# tiny13_charlie4_50mm_AAA_optical_diag_SM.net
KiCad netlist of a schematic drawn in EAGLE
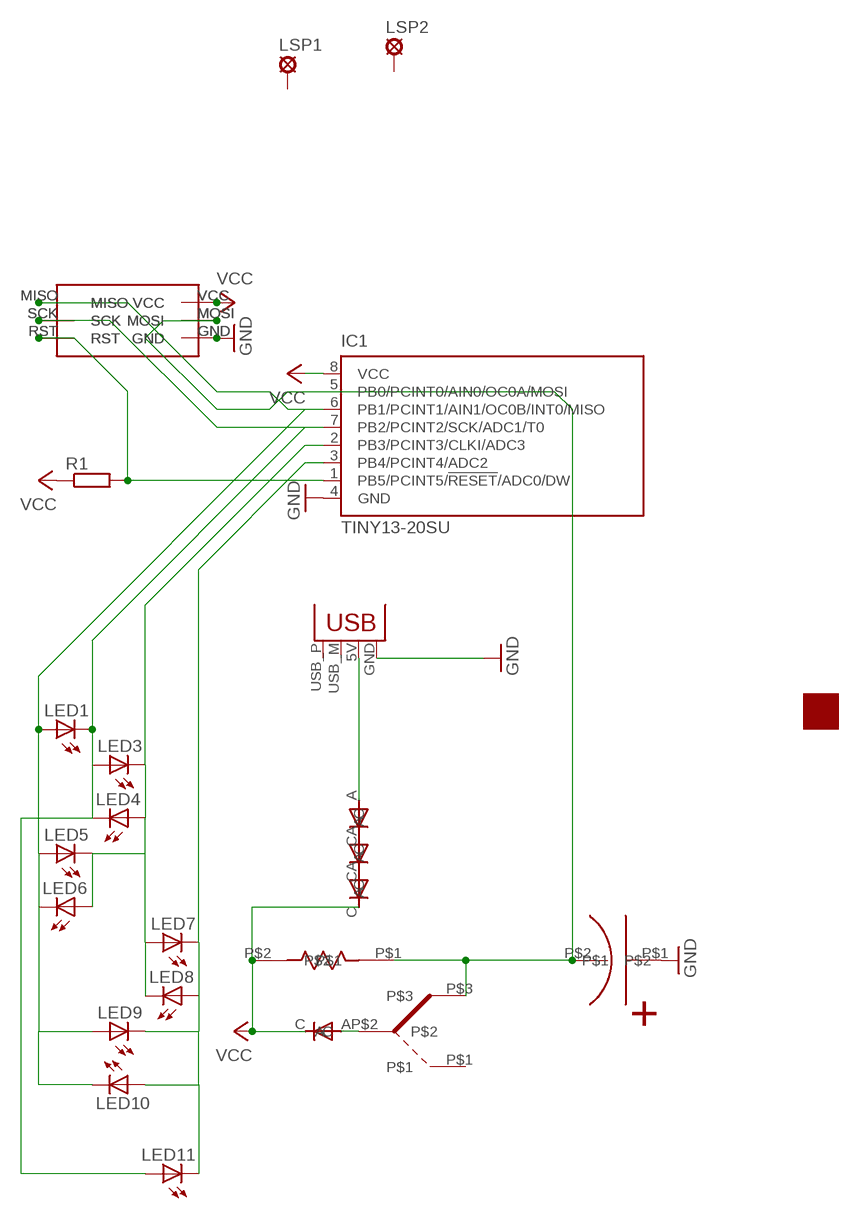
[diagram p0: schematic, sheet 1]

(export (version "E")
  (design (tool "Eeschema 10.0.6"))
  (components
    (comp (ref "IC1")
      (value "TINY13-20SU")
      (footprint "eagle-import:8S2")
      (fields
        (field (name "MPN") "ATTINY13-20SU")
        (field (name "MPN_1") "ATTINY13-20SU")
        (field (name "OC_FARNELL") "9171568")
        (field (name "OC_NEWARK") "96K6522")
      )
      (libsource (lib "eagle-import") (part "TINY13SU-20"))
    )
    (comp (ref "LED1")
      (value "LED3MM")
      (footprint "eagle-import:LED3MM")
      (libsource (lib "eagle-import") (part "LED3MM"))
    )
    (comp (ref "LED3")
      (value "LED3MM")
      (footprint "eagle-import:LED3MM")
      (libsource (lib "eagle-import") (part "LED3MM"))
    )
    (comp (ref "LED4")
      (value "LED3MM")
      (footprint "eagle-import:LED3MM")
      (libsource (lib "eagle-import") (part "LED3MM"))
    )
    (comp (ref "LED5")
      (value "LED3MM")
      (footprint "eagle-import:LED3MM")
      (libsource (lib "eagle-import") (part "LED3MM"))
    )
    (comp (ref "LED6")
      (value "LED3MM")
      (footprint "eagle-import:LED3MM")
      (libsource (lib "eagle-import") (part "LED3MM"))
    )
    (comp (ref "LED7")
      (value "LED3MM")
      (footprint "eagle-import:LED3MM")
      (libsource (lib "eagle-import") (part "LED3MM"))
    )
    (comp (ref "LED8")
      (value "LED3MM")
      (footprint "eagle-import:LED3MM")
      (libsource (lib "eagle-import") (part "LED3MM"))
    )
    (comp (ref "LED9")
      (value "LED3MM")
      (footprint "eagle-import:LED3MM")
      (libsource (lib "eagle-import") (part "LED3MM"))
    )
    (comp (ref "LED10")
      (value "LED3MM")
      (footprint "eagle-import:LED3MM")
      (libsource (lib "eagle-import") (part "LED3MM"))
    )
    (comp (ref "LED11")
      (value "LED3MM")
      (footprint "eagle-import:LED3MM")
      (libsource (lib "eagle-import") (part "LED3MM"))
    )
    (comp (ref "LSP1")
      (value "LSP10")
      (footprint "eagle-import:LSP10")
      (libsource (lib "eagle-import") (part "LSP10"))
    )
    (comp (ref "LSP2")
      (value "LSP10")
      (footprint "eagle-import:LSP10")
      (libsource (lib "eagle-import") (part "LSP10"))
    )
    (comp (ref "R1")
      (value "R-EU_0204/5")
      (footprint "eagle-import:0204_5")
      (libsource (lib "eagle-import") (part "R-EU_0204/5"))
    )
    (comp (ref "U$1")
      (value "R-6")
      (footprint "eagle-import:R-6")
      (libsource (lib "eagle-import") (part "R-6"))
    )
    (comp (ref "U$2")
      (value "D-6")
      (footprint "eagle-import:D-7.5")
      (libsource (lib "eagle-import") (part "D-6"))
    )
    (comp (ref "U$3")
      (value "D-6")
      (footprint "eagle-import:D-7.5")
      (libsource (lib "eagle-import") (part "D-6"))
    )
    (comp (ref "U$4")
      (value "AVR_ISP_6_PIN_1X6_SMT_SQUARE_ROUNDED")
      (footprint "eagle-import:CONTACT_ISP_1X6_SQUARE_PAD_ROUNDED")
      (libsource (lib "eagle-import") (part "AVR_ISP_6_PIN_1X6_SMT_SQUARE_ROUNDED"))
    )
    (comp (ref "U$5")
      (value "NICHICON_12F")
      (footprint "eagle-import:NICHICON_10X30")
      (libsource (lib "eagle-import") (part "NICHICON_12F"))
    )
    (comp (ref "U$6")
      (value "D-6")
      (footprint "eagle-import:D-7.5")
      (libsource (lib "eagle-import") (part "D-6"))
    )
    (comp (ref "U$7")
      (value "D-6")
      (footprint "eagle-import:D-7.5")
      (libsource (lib "eagle-import") (part "D-6"))
    )
    (comp (ref "U$8")
      (value "SPST_SWITCH_MICRO_PTH")
      (footprint "eagle-import:SPSTMICRO")
      (libsource (lib "eagle-import") (part "SPST_SWITCH_MICRO_PTH"))
    )
    (comp (ref "U$9")
      (value "AVR_ISP_6_PIN_1X6_SMT_SQUARE_ROUNDED")
      (footprint "eagle-import:CONTACT_ISP_1X6_SQUARE_PAD_ROUNDED")
      (libsource (lib "eagle-import") (part "AVR_ISP_6_PIN_1X6_SMT_SQUARE_ROUNDED"))
    )
    (comp (ref "U$10")
      (value "LOGO")
      (footprint "eagle-import:LOGO")
      (libsource (lib "eagle-import") (part "LOGO"))
    )
    (comp (ref "X1")
      (value "USBPCB")
      (footprint "eagle-import:USB-A-PCB")
      (libsource (lib "eagle-import") (part "USBPCB"))
    )
  )
  (nets
    (net (code "1") (name "GND") (class "Default")
      (node (ref "IC1") (pin "4") (pinfunction "GND_4") (pintype "power_in"))
      (node (ref "U$4") (pin "GND") (pinfunction "GND_GND") (pintype "bidirectional"))
      (node (ref "U$5") (pin "P$1") (pinfunction "P$1_P$1") (pintype "bidirectional"))
      (node (ref "U$9") (pin "GND") (pinfunction "GND_GND") (pintype "bidirectional"))
      (node (ref "X1") (pin "GND") (pinfunction "GND_GND") (pintype "bidirectional"))
    )
    (net (code "2") (name "Net-(IC1-PB0{slash}PCINT0{slash}AIN0{slash}OC0A{slash}MOSI)") (class "Default")
      (node (ref "IC1") (pin "5") (pinfunction "PB0/PCINT0/AIN0/OC0A/MOSI_5") (pintype "bidirectional"))
      (node (ref "U$1") (pin "P$1") (pinfunction "P$1_P$1") (pintype "bidirectional"))
      (node (ref "U$4") (pin "MOSI") (pinfunction "MOSI_MOSI") (pintype "bidirectional"))
      (node (ref "U$5") (pin "P$2") (pinfunction "P$2_P$2") (pintype "bidirectional"))
      (node (ref "U$8") (pin "P$3") (pinfunction "P$3_P$3") (pintype "bidirectional"))
      (node (ref "U$9") (pin "MOSI") (pinfunction "MOSI_MOSI") (pintype "bidirectional"))
    )
    (net (code "3") (name "Net-(IC1-PB1{slash}PCINT1{slash}AIN1{slash}OC0B{slash}INT0{slash}MISO)") (class "Default")
      (node (ref "IC1") (pin "6") (pinfunction "PB1/PCINT1/AIN1/OC0B/INT0/MISO_6") (pintype "bidirectional"))
      (node (ref "LED1") (pin "A") (pinfunction "A_A") (pintype "passive"))
      (node (ref "LED10") (pin "K") (pinfunction "C_K") (pintype "passive"))
      (node (ref "LED5") (pin "A") (pinfunction "A_A") (pintype "passive"))
      (node (ref "LED6") (pin "K") (pinfunction "C_K") (pintype "passive"))
      (node (ref "LED9") (pin "A") (pinfunction "A_A") (pintype "passive"))
      (node (ref "U$4") (pin "MISO") (pinfunction "MISO_MISO") (pintype "bidirectional"))
      (node (ref "U$9") (pin "MISO") (pinfunction "MISO_MISO") (pintype "bidirectional"))
    )
    (net (code "4") (name "Net-(IC1-PB2{slash}PCINT2{slash}SCK{slash}ADC1{slash}T0)") (class "Default")
      (node (ref "IC1") (pin "7") (pinfunction "PB2/PCINT2/SCK/ADC1/T0_7") (pintype "bidirectional"))
      (node (ref "LED1") (pin "K") (pinfunction "C_K") (pintype "passive"))
      (node (ref "LED11") (pin "A") (pinfunction "A_A") (pintype "passive"))
      (node (ref "LED3") (pin "A") (pinfunction "A_A") (pintype "passive"))
      (node (ref "LED4") (pin "K") (pinfunction "C_K") (pintype "passive"))
      (node (ref "U$4") (pin "SCK") (pinfunction "SCK_SCK") (pintype "bidirectional"))
      (node (ref "U$9") (pin "SCK") (pinfunction "SCK_SCK") (pintype "bidirectional"))
    )
    (net (code "5") (name "Net-(IC1-PB3{slash}PCINT3{slash}CLKI{slash}ADC3)") (class "Default")
      (node (ref "IC1") (pin "2") (pinfunction "PB3/PCINT3/CLKI/ADC3_2") (pintype "bidirectional"))
      (node (ref "LED3") (pin "K") (pinfunction "C_K") (pintype "passive"))
      (node (ref "LED4") (pin "A") (pinfunction "A_A") (pintype "passive"))
      (node (ref "LED5") (pin "K") (pinfunction "C_K") (pintype "passive"))
      (node (ref "LED6") (pin "A") (pinfunction "A_A") (pintype "passive"))
      (node (ref "LED7") (pin "A") (pinfunction "A_A") (pintype "passive"))
      (node (ref "LED8") (pin "K") (pinfunction "C_K") (pintype "passive"))
    )
    (net (code "6") (name "Net-(IC1-PB4{slash}PCINT4{slash}ADC2)") (class "Default")
      (node (ref "IC1") (pin "3") (pinfunction "PB4/PCINT4/ADC2_3") (pintype "bidirectional"))
      (node (ref "LED10") (pin "A") (pinfunction "A_A") (pintype "passive"))
      (node (ref "LED11") (pin "K") (pinfunction "C_K") (pintype "passive"))
      (node (ref "LED7") (pin "K") (pinfunction "C_K") (pintype "passive"))
      (node (ref "LED8") (pin "A") (pinfunction "A_A") (pintype "passive"))
      (node (ref "LED9") (pin "K") (pinfunction "C_K") (pintype "passive"))
    )
    (net (code "7") (name "Net-(IC1-PB5{slash}PCINT5{slash}~{RESET}{slash}ADC0{slash}DW)") (class "Default")
      (node (ref "IC1") (pin "1") (pinfunction "PB5/PCINT5/~{RESET}/ADC0/DW_1") (pintype "bidirectional"))
      (node (ref "R1") (pin "2") (pinfunction "2_2") (pintype "passive"))
      (node (ref "U$4") (pin "RST") (pinfunction "RST_RST") (pintype "bidirectional"))
      (node (ref "U$9") (pin "RST") (pinfunction "RST_RST") (pintype "bidirectional"))
    )
    (net (code "8") (name "Net-(U$2-PadC)") (class "Default")
      (node (ref "U$2") (pin "C") (pinfunction "C_C") (pintype "bidirectional"))
      (node (ref "U$3") (pin "A") (pinfunction "A_A") (pintype "bidirectional"))
    )
    (net (code "9") (name "Net-(U$3-PadC)") (class "Default")
      (node (ref "U$3") (pin "C") (pinfunction "C_C") (pintype "bidirectional"))
      (node (ref "U$6") (pin "A") (pinfunction "A_A") (pintype "bidirectional"))
    )
    (net (code "10") (name "Net-(U$7-PadA)") (class "Default")
      (node (ref "U$7") (pin "A") (pinfunction "A_A") (pintype "bidirectional"))
      (node (ref "U$8") (pin "P$2") (pinfunction "P$2_P$2") (pintype "bidirectional"))
    )
    (net (code "11") (name "Net-(X1-VBUS)") (class "Default")
      (node (ref "U$2") (pin "A") (pinfunction "A_A") (pintype "bidirectional"))
      (node (ref "X1") (pin "5V") (pinfunction "VBUS_5V") (pintype "bidirectional"))
    )
    (net (code "12") (name "VCC") (class "Default")
      (node (ref "IC1") (pin "8") (pinfunction "VCC_8") (pintype "power_in"))
      (node (ref "R1") (pin "1") (pinfunction "1_1") (pintype "passive"))
      (node (ref "U$1") (pin "P$2") (pinfunction "P$2_P$2") (pintype "bidirectional"))
      (node (ref "U$4") (pin "VCC") (pinfunction "VCC_VCC") (pintype "bidirectional"))
      (node (ref "U$6") (pin "C") (pinfunction "C_C") (pintype "bidirectional"))
      (node (ref "U$7") (pin "C") (pinfunction "C_C") (pintype "bidirectional"))
      (node (ref "U$9") (pin "VCC") (pinfunction "VCC_VCC") (pintype "bidirectional"))
    )
    (net (code "13") (name "unconnected-(LSP1-PadMP)") (class "Default")
      (node (ref "LSP1") (pin "MP") (pinfunction "MP_MP") (pintype "passive"))
    )
    (net (code "14") (name "unconnected-(LSP2-PadMP)") (class "Default")
      (node (ref "LSP2") (pin "MP") (pinfunction "MP_MP") (pintype "passive"))
    )
    (net (code "15") (name "unconnected-(U$8-PadP$1)") (class "Default")
      (node (ref "U$8") (pin "P$1") (pinfunction "P$1_P$1") (pintype "bidirectional"))
    )
    (net (code "16") (name "unconnected-(X1-D+-PadUSB_P)") (class "Default")
      (node (ref "X1") (pin "USB_P") (pinfunction "D+_USB_P") (pintype "bidirectional"))
    )
    (net (code "17") (name "unconnected-(X1-D--PadUSB_M)") (class "Default")
      (node (ref "X1") (pin "USB_M") (pinfunction "D-_USB_M") (pintype "bidirectional"))
    )
  )
)
